# TA_3.net
KiCad netlist of a schematic drawn in EAGLE
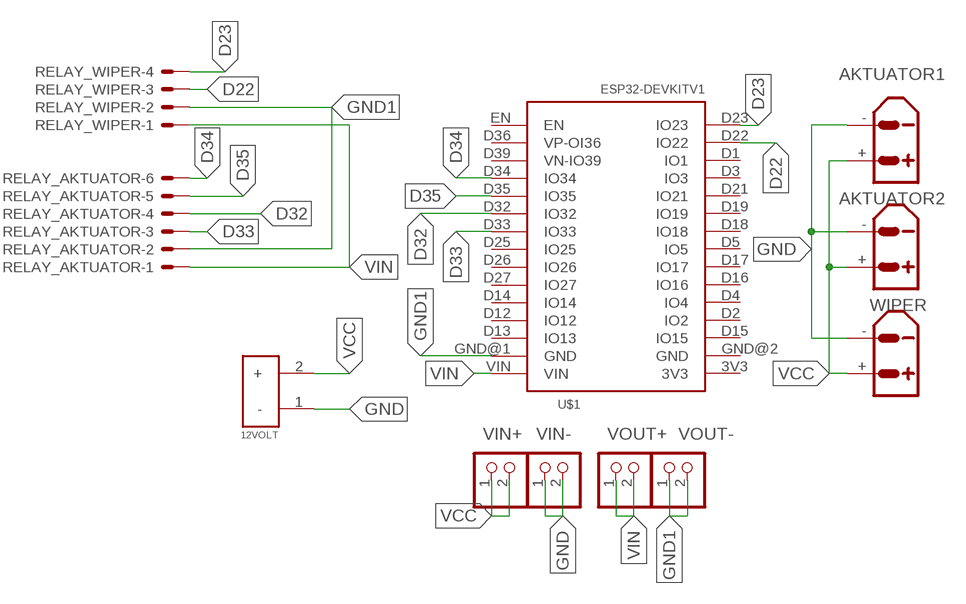
[diagram p0: schematic, sheet 1]

(export (version "E")
  (design (tool "Eeschema 10.0.6"))
  (components
    (comp (ref "12VOLT")
      (value "XT60-M")
      (footprint "eagle-import:AMASS_XT60-M")
      (fields (field (name "MF") "AMASS"))
      (libsource (lib "eagle-import") (part "XT60-M"))
    )
    (comp (ref "AKTUATOR1")
      (value "XT30UPB-F")
      (footprint "eagle-import:XT30UPB-F")
      (libsource (lib "eagle-import") (part "XT30UPB-F"))
    )
    (comp (ref "AKTUATOR2")
      (value "XT30UPB-F")
      (footprint "eagle-import:XT30UPB-F")
      (libsource (lib "eagle-import") (part "XT30UPB-F"))
    )
    (comp (ref "RELAY_AKTUATOR")
      (value "JST-XH-06-PIN-LONG-PAD")
      (footprint "eagle-import:JST-XH-06-PACKAGE-LONG-PAD")
      (libsource (lib "eagle-import") (part "JST-XH-06-PIN-LONG-PAD"))
    )
    (comp (ref "RELAY_WIPER")
      (value "JST-XH-04-PIN-LONG-PAD")
      (footprint "eagle-import:JST-XH-04-PACKAGE-LONG-PAD")
      (libsource (lib "eagle-import") (part "JST-XH-04-PIN-LONG-PAD"))
    )
    (comp (ref "U$1")
      (value "ESP32DEVKITV1")
      (footprint "eagle-import:ESP32-DEVKITV1")
      (libsource (lib "eagle-import") (part "ESP32DEVKITV1"))
    )
    (comp (ref "VIN+")
      (value "PINHD-1X2")
      (footprint "eagle-import:1X02")
      (libsource (lib "eagle-import") (part "PINHD-1X2"))
    )
    (comp (ref "VIN-")
      (value "PINHD-1X2")
      (footprint "eagle-import:1X02")
      (libsource (lib "eagle-import") (part "PINHD-1X2"))
    )
    (comp (ref "VOUT+")
      (value "PINHD-1X2")
      (footprint "eagle-import:1X02")
      (libsource (lib "eagle-import") (part "PINHD-1X2"))
    )
    (comp (ref "VOUT-")
      (value "PINHD-1X2")
      (footprint "eagle-import:1X02")
      (libsource (lib "eagle-import") (part "PINHD-1X2"))
    )
    (comp (ref "WIPER")
      (value "XT30UPB-F")
      (footprint "eagle-import:XT30UPB-F")
      (libsource (lib "eagle-import") (part "XT30UPB-F"))
    )
  )
  (nets
    (net (code "1") (name "D22") (class "Default")
      (node (ref "RELAY_WIPER") (pin "3") (pinfunction "S_3") (pintype "passive"))
      (node (ref "U$1") (pin "D22") (pinfunction "IO22_D22") (pintype "bidirectional"))
    )
    (net (code "2") (name "D23") (class "Default")
      (node (ref "RELAY_WIPER") (pin "4") (pinfunction "S_4") (pintype "passive"))
      (node (ref "U$1") (pin "D23") (pinfunction "IO23_D23") (pintype "bidirectional"))
    )
    (net (code "3") (name "D32") (class "Default")
      (node (ref "RELAY_AKTUATOR") (pin "4") (pinfunction "S_4") (pintype "passive"))
      (node (ref "U$1") (pin "D32") (pinfunction "IO32_D32") (pintype "bidirectional"))
    )
    (net (code "4") (name "D33") (class "Default")
      (node (ref "RELAY_AKTUATOR") (pin "3") (pinfunction "S_3") (pintype "passive"))
      (node (ref "U$1") (pin "D33") (pinfunction "IO33_D33") (pintype "bidirectional"))
    )
    (net (code "5") (name "D34") (class "Default")
      (node (ref "RELAY_AKTUATOR") (pin "6") (pinfunction "S_6") (pintype "passive"))
      (node (ref "U$1") (pin "D34") (pinfunction "IO34_D34") (pintype "bidirectional"))
    )
    (net (code "6") (name "D35") (class "Default")
      (node (ref "RELAY_AKTUATOR") (pin "5") (pinfunction "S_5") (pintype "passive"))
      (node (ref "U$1") (pin "D35") (pinfunction "IO35_D35") (pintype "bidirectional"))
    )
    (net (code "7") (name "GND") (class "Default")
      (node (ref "12VOLT") (pin "1") (pinfunction "-_1") (pintype "passive"))
      (node (ref "AKTUATOR1") (pin "-") (pinfunction "-_-") (pintype "power_in"))
      (node (ref "AKTUATOR2") (pin "-") (pinfunction "-_-") (pintype "power_in"))
      (node (ref "VIN-") (pin "1") (pinfunction "1_1") (pintype "passive"))
      (node (ref "VIN-") (pin "2") (pinfunction "2_2") (pintype "passive"))
      (node (ref "WIPER") (pin "-") (pinfunction "-_-") (pintype "power_in"))
    )
    (net (code "8") (name "GND1") (class "Default")
      (node (ref "RELAY_AKTUATOR") (pin "2") (pinfunction "S_2") (pintype "passive"))
      (node (ref "RELAY_WIPER") (pin "2") (pinfunction "S_2") (pintype "passive"))
      (node (ref "U$1") (pin "GND@1") (pinfunction "GND_GND@1") (pintype "bidirectional"))
      (node (ref "VOUT-") (pin "1") (pinfunction "1_1") (pintype "passive"))
      (node (ref "VOUT-") (pin "2") (pinfunction "2_2") (pintype "passive"))
    )
    (net (code "9") (name "VCC") (class "Default")
      (node (ref "12VOLT") (pin "2") (pinfunction "+_2") (pintype "passive"))
      (node (ref "AKTUATOR1") (pin "+") (pinfunction "+_+") (pintype "power_in"))
      (node (ref "AKTUATOR2") (pin "+") (pinfunction "+_+") (pintype "power_in"))
      (node (ref "VIN+") (pin "1") (pinfunction "1_1") (pintype "passive"))
      (node (ref "VIN+") (pin "2") (pinfunction "2_2") (pintype "passive"))
      (node (ref "WIPER") (pin "+") (pinfunction "+_+") (pintype "power_in"))
    )
    (net (code "10") (name "VIN") (class "Default")
      (node (ref "RELAY_AKTUATOR") (pin "1") (pinfunction "S_1") (pintype "passive"))
      (node (ref "RELAY_WIPER") (pin "1") (pinfunction "S_1") (pintype "passive"))
      (node (ref "U$1") (pin "VIN") (pinfunction "VIN_VIN") (pintype "bidirectional"))
      (node (ref "VOUT+") (pin "1") (pinfunction "1_1") (pintype "passive"))
      (node (ref "VOUT+") (pin "2") (pinfunction "2_2") (pintype "passive"))
    )
    (net (code "11") (name "unconnected-(U$1-GND-PadGND@2)") (class "Default")
      (node (ref "U$1") (pin "GND@2") (pinfunction "GND_GND@2") (pintype "bidirectional"))
    )
    (net (code "12") (name "unconnected-(U$1-IO1-PadD1)") (class "Default")
      (node (ref "U$1") (pin "D1") (pinfunction "IO1_D1") (pintype "bidirectional"))
    )
    (net (code "13") (name "unconnected-(U$1-IO2-PadD2)") (class "Default")
      (node (ref "U$1") (pin "D2") (pinfunction "IO2_D2") (pintype "bidirectional"))
    )
    (net (code "14") (name "unconnected-(U$1-IO3-PadD3)") (class "Default")
      (node (ref "U$1") (pin "D3") (pinfunction "IO3_D3") (pintype "bidirectional"))
    )
    (net (code "15") (name "unconnected-(U$1-IO4-PadD4)") (class "Default")
      (node (ref "U$1") (pin "D4") (pinfunction "IO4_D4") (pintype "bidirectional"))
    )
    (net (code "16") (name "unconnected-(U$1-IO5-PadD5)") (class "Default")
      (node (ref "U$1") (pin "D5") (pinfunction "IO5_D5") (pintype "bidirectional"))
    )
    (net (code "17") (name "unconnected-(U$1-IO12-PadD12)") (class "Default")
      (node (ref "U$1") (pin "D12") (pinfunction "IO12_D12") (pintype "bidirectional"))
    )
    (net (code "18") (name "unconnected-(U$1-IO13-PadD13)") (class "Default")
      (node (ref "U$1") (pin "D13") (pinfunction "IO13_D13") (pintype "bidirectional"))
    )
    (net (code "19") (name "unconnected-(U$1-IO14-PadD14)") (class "Default")
      (node (ref "U$1") (pin "D14") (pinfunction "IO14_D14") (pintype "bidirectional"))
    )
    (net (code "20") (name "unconnected-(U$1-IO15-PadD15)") (class "Default")
      (node (ref "U$1") (pin "D15") (pinfunction "IO15_D15") (pintype "bidirectional"))
    )
    (net (code "21") (name "unconnected-(U$1-IO16-PadD16)") (class "Default")
      (node (ref "U$1") (pin "D16") (pinfunction "IO16_D16") (pintype "bidirectional"))
    )
    (net (code "22") (name "unconnected-(U$1-IO17-PadD17)") (class "Default")
      (node (ref "U$1") (pin "D17") (pinfunction "IO17_D17") (pintype "bidirectional"))
    )
    (net (code "23") (name "unconnected-(U$1-IO18-PadD18)") (class "Default")
      (node (ref "U$1") (pin "D18") (pinfunction "IO18_D18") (pintype "bidirectional"))
    )
    (net (code "24") (name "unconnected-(U$1-IO19-PadD19)") (class "Default")
      (node (ref "U$1") (pin "D19") (pinfunction "IO19_D19") (pintype "bidirectional"))
    )
    (net (code "25") (name "unconnected-(U$1-IO21-PadD21)") (class "Default")
      (node (ref "U$1") (pin "D21") (pinfunction "IO21_D21") (pintype "bidirectional"))
    )
    (net (code "26") (name "unconnected-(U$1-IO25-PadD25)") (class "Default")
      (node (ref "U$1") (pin "D25") (pinfunction "IO25_D25") (pintype "bidirectional"))
    )
    (net (code "27") (name "unconnected-(U$1-IO26-PadD26)") (class "Default")
      (node (ref "U$1") (pin "D26") (pinfunction "IO26_D26") (pintype "bidirectional"))
    )
    (net (code "28") (name "unconnected-(U$1-IO27-PadD27)") (class "Default")
      (node (ref "U$1") (pin "D27") (pinfunction "IO27_D27") (pintype "bidirectional"))
    )
    (net (code "29") (name "unconnected-(U$1-Pad3V3)") (class "Default")
      (node (ref "U$1") (pin "3V3") (pinfunction "3V3_3V3") (pintype "bidirectional"))
    )
    (net (code "30") (name "unconnected-(U$1-PadEN)") (class "Default")
      (node (ref "U$1") (pin "EN") (pinfunction "EN_EN") (pintype "bidirectional"))
    )
    (net (code "31") (name "unconnected-(U$1-VN-IO39-PadD39)") (class "Default")
      (node (ref "U$1") (pin "D39") (pinfunction "VN-IO39_D39") (pintype "bidirectional"))
    )
    (net (code "32") (name "unconnected-(U$1-VP-OI36-PadD36)") (class "Default")
      (node (ref "U$1") (pin "D36") (pinfunction "VP-OI36_D36") (pintype "bidirectional"))
    )
  )
)
